# ardumashtun_opl_v1.net
KiCad netlist of a schematic drawn in EAGLE
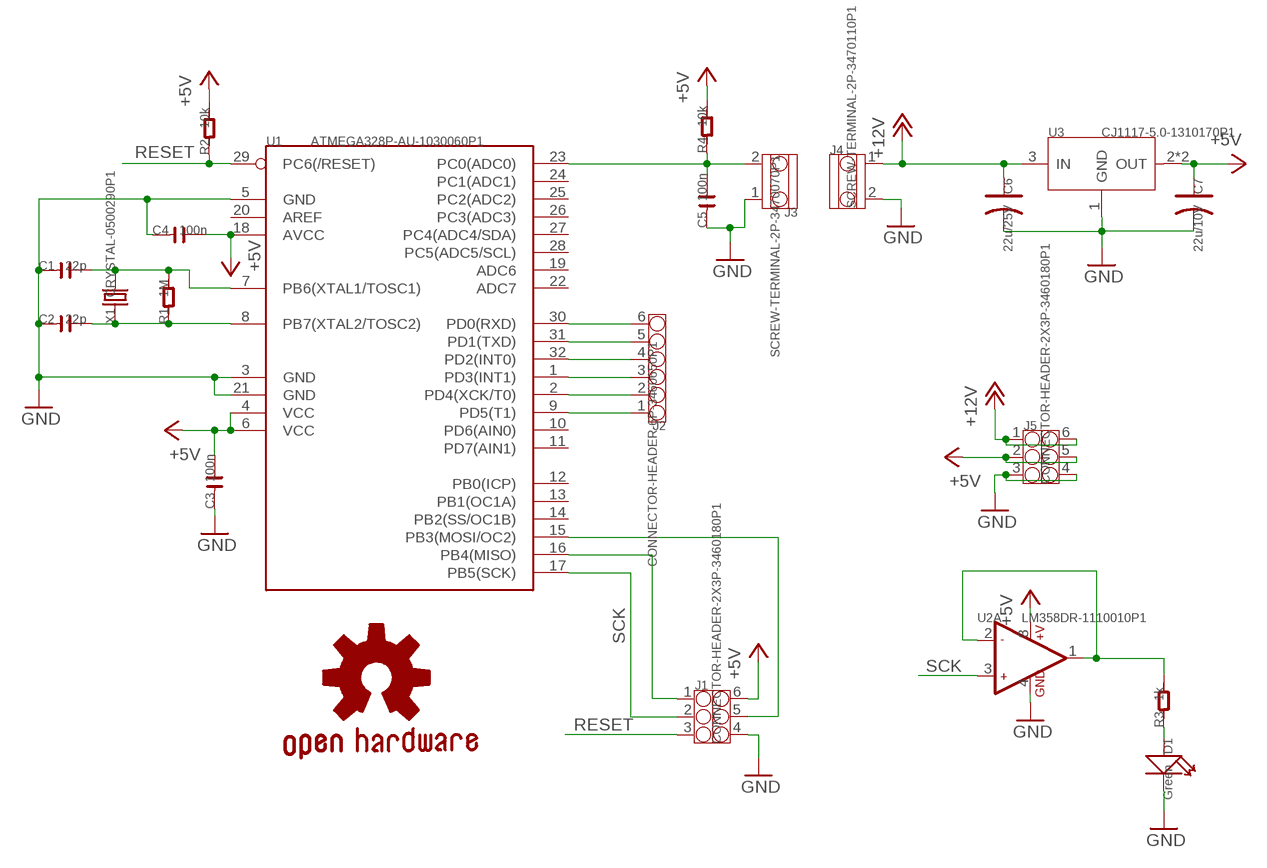
[diagram p0: schematic, sheet 1]

(export (version "E")
  (design (tool "Eeschema 10.0.6"))
  (components
    (comp (ref "C1")
      (value "22p")
      (footprint "eagle-import:C0603")
      (libsource (lib "eagle-import") (part "C-0603"))
    )
    (comp (ref "C2")
      (value "22p")
      (footprint "eagle-import:C0603")
      (libsource (lib "eagle-import") (part "C-0603"))
    )
    (comp (ref "C3")
      (value "100n")
      (footprint "eagle-import:C0603")
      (libsource (lib "eagle-import") (part "C-0603"))
    )
    (comp (ref "C4")
      (value "100n")
      (footprint "eagle-import:C0603")
      (libsource (lib "eagle-import") (part "C-0603"))
    )
    (comp (ref "C5")
      (value "100n")
      (footprint "eagle-import:C0603")
      (libsource (lib "eagle-import") (part "C-0603"))
    )
    (comp (ref "C6")
      (value "22u/25V")
      (footprint "eagle-import:AVX-C")
      (libsource (lib "eagle-import") (part "C-POLAR-C"))
    )
    (comp (ref "C7")
      (value "22u/10V")
      (footprint "eagle-import:AVX-B")
      (libsource (lib "eagle-import") (part "C-POLAR-B"))
    )
    (comp (ref "D1")
      (value "Green")
      (footprint "eagle-import:LED0603")
      (libsource (lib "eagle-import") (part "LED"))
    )
    (comp (ref "GOLD_ORB_SM1")
      (value "OSHWLOGO_GOLD_ORB_SM")
      (footprint "eagle-import:OSHW2")
      (libsource (lib "eagle-import") (part "OSHWLOGO_GOLD_ORB_SM"))
    )
    (comp (ref "J1")
      (value "CONNECTOR-HEADER-2X3P-3460180P1")
      (footprint "eagle-import:2X3P-2.54-2.54-11.6-3.0-BLACK-MALE")
      (libsource (lib "eagle-import") (part "CONNECTOR-HEADER-2X3P-3460180P1"))
    )
    (comp (ref "J2")
      (value "CONNECTOR-HEADER-6P-3460650P1")
      (footprint "eagle-import:1X6P-2.54-2.54-11.6-3.0-BLACK-MALE")
      (libsource (lib "eagle-import") (part "CONNECTOR-HEADER-6P-3460650P1"))
    )
    (comp (ref "J3")
      (value "SCREW-TERMINAL-2P-3470070P1")
      (footprint "eagle-import:2P-3.5")
      (libsource (lib "eagle-import") (part "SCREW-TERMINAL-2P-3470070P1"))
    )
    (comp (ref "J4")
      (value "SCREW-TERMINAL-2P-3470110P1")
      (footprint "eagle-import:2P-5.0")
      (libsource (lib "eagle-import") (part "SCREW-TERMINAL-2P-3470110P1"))
    )
    (comp (ref "J5")
      (value "CONNECTOR-HEADER-2X3P-3460180P1")
      (footprint "eagle-import:2X3P-2.54-2.54-11.6-3.0-BLACK-MALE")
      (libsource (lib "eagle-import") (part "CONNECTOR-HEADER-2X3P-3460180P1"))
    )
    (comp (ref "R1")
      (value "1M")
      (footprint "eagle-import:R0603")
      (libsource (lib "eagle-import") (part "R-0603"))
    )
    (comp (ref "R2")
      (value "10k")
      (footprint "eagle-import:R0603")
      (libsource (lib "eagle-import") (part "R-0603"))
    )
    (comp (ref "R3")
      (value "1k")
      (footprint "eagle-import:R0603")
      (libsource (lib "eagle-import") (part "R-0603"))
    )
    (comp (ref "R4")
      (value "10k")
      (footprint "eagle-import:R0603")
      (libsource (lib "eagle-import") (part "R-0603"))
    )
    (comp (ref "U1")
      (value "ATMEGA328P-AU-1030060P1")
      (footprint "eagle-import:TQFP32")
      (libsource (lib "eagle-import") (part "ATMEGA328P-AU-1030060P1"))
    )
    (comp (ref "U2")
      (value "LM358DR-1110010P1")
      (footprint "eagle-import:SOIC8")
      (libsource (lib "eagle-import") (part "LM358DR-1110010P1"))
    )
    (comp (ref "U3")
      (value "CJ1117-5.0-1310170P1")
      (footprint "eagle-import:SOT223")
      (libsource (lib "eagle-import") (part "CJ1117-5.0-1310170P1"))
    )
    (comp (ref "X1")
      (value "CRYSTAL-0500290P1")
      (footprint "eagle-import:2P-SMD-5.0X3.2")
      (libsource (lib "eagle-import") (part "CRYSTAL-0500290P1"))
    )
  )
  (nets
    (net (code "1") (name "+5V") (class "Default")
      (node (ref "C3") (pin "2") (pinfunction "2_2") (pintype "bidirectional"))
      (node (ref "C4") (pin "2") (pinfunction "2_2") (pintype "bidirectional"))
      (node (ref "C7") (pin "+") (pinfunction "1_+") (pintype "bidirectional"))
      (node (ref "J1") (pin "6") (pinfunction "6_6") (pintype "bidirectional"))
      (node (ref "J5") (pin "2") (pinfunction "2_2") (pintype "bidirectional"))
      (node (ref "J5") (pin "5") (pinfunction "5_5") (pintype "bidirectional"))
      (node (ref "R2") (pin "2") (pinfunction "2_2") (pintype "bidirectional"))
      (node (ref "R4") (pin "2") (pinfunction "2_2") (pintype "bidirectional"))
      (node (ref "U1") (pin "18") (pinfunction "AVCC_18") (pintype "bidirectional"))
      (node (ref "U1") (pin "4") (pinfunction "VCC_4") (pintype "bidirectional"))
      (node (ref "U1") (pin "6") (pinfunction "VCC_6") (pintype "bidirectional"))
      (node (ref "U2") (pin "8") (pinfunction "+V_8") (pintype "power_in"))
      (node (ref "U3") (pin "2") (pinfunction "OUT_2") (pintype "bidirectional"))
      (node (ref "U3") (pin "TER") (pinfunction "OUT_TER") (pintype "bidirectional"))
    )
    (net (code "2") (name "+12V") (class "Default")
      (node (ref "C6") (pin "+") (pinfunction "1_+") (pintype "bidirectional"))
      (node (ref "J4") (pin "1") (pinfunction "1_1") (pintype "bidirectional"))
      (node (ref "J5") (pin "1") (pinfunction "1_1") (pintype "bidirectional"))
      (node (ref "J5") (pin "6") (pinfunction "6_6") (pintype "bidirectional"))
      (node (ref "U3") (pin "3") (pinfunction "IN_3") (pintype "bidirectional"))
    )
    (net (code "3") (name "/RESET") (class "Default")
      (node (ref "J1") (pin "3") (pinfunction "3_3") (pintype "bidirectional"))
      (node (ref "R2") (pin "1") (pinfunction "1_1") (pintype "bidirectional"))
      (node (ref "U1") (pin "29") (pinfunction "PC6(/RESET)_29") (pintype "bidirectional"))
    )
    (net (code "4") (name "/SCK") (class "Default")
      (node (ref "J1") (pin "2") (pinfunction "2_2") (pintype "bidirectional"))
      (node (ref "U1") (pin "17") (pinfunction "PB5(SCK)_17") (pintype "bidirectional"))
      (node (ref "U2") (pin "3") (pinfunction "+IN1_3") (pintype "input"))
    )
    (net (code "5") (name "GND") (class "Default")
      (node (ref "C1") (pin "1") (pinfunction "1_1") (pintype "bidirectional"))
      (node (ref "C2") (pin "1") (pinfunction "1_1") (pintype "bidirectional"))
      (node (ref "C3") (pin "1") (pinfunction "1_1") (pintype "bidirectional"))
      (node (ref "C4") (pin "1") (pinfunction "1_1") (pintype "bidirectional"))
      (node (ref "C5") (pin "1") (pinfunction "1_1") (pintype "bidirectional"))
      (node (ref "C6") (pin "-") (pinfunction "2_-") (pintype "bidirectional"))
      (node (ref "C7") (pin "-") (pinfunction "2_-") (pintype "bidirectional"))
      (node (ref "D1") (pin "-") (pinfunction "-_-") (pintype "passive"))
      (node (ref "J1") (pin "4") (pinfunction "4_4") (pintype "bidirectional"))
      (node (ref "J3") (pin "1") (pinfunction "1_1") (pintype "bidirectional"))
      (node (ref "J4") (pin "2") (pinfunction "2_2") (pintype "bidirectional"))
      (node (ref "J5") (pin "3") (pinfunction "3_3") (pintype "bidirectional"))
      (node (ref "J5") (pin "4") (pinfunction "4_4") (pintype "bidirectional"))
      (node (ref "U1") (pin "21") (pinfunction "GND_21") (pintype "bidirectional"))
      (node (ref "U1") (pin "3") (pinfunction "GND_3") (pintype "bidirectional"))
      (node (ref "U1") (pin "5") (pinfunction "GND_5") (pintype "bidirectional"))
      (node (ref "U2") (pin "4") (pinfunction "GND_4") (pintype "power_in"))
      (node (ref "U3") (pin "1") (pinfunction "GND_1") (pintype "bidirectional"))
    )
    (net (code "6") (name "Net-(D1-Pad+)") (class "Default")
      (node (ref "D1") (pin "+") (pinfunction "+_+") (pintype "passive"))
      (node (ref "R3") (pin "1") (pinfunction "1_1") (pintype "bidirectional"))
    )
    (net (code "7") (name "Net-(U1-PB3(MOSI{slash}OC2))") (class "Default")
      (node (ref "J1") (pin "5") (pinfunction "5_5") (pintype "bidirectional"))
      (node (ref "U1") (pin "15") (pinfunction "PB3(MOSI/OC2)_15") (pintype "bidirectional"))
    )
    (net (code "8") (name "Net-(U1-PB4(MISO))") (class "Default")
      (node (ref "J1") (pin "1") (pinfunction "1_1") (pintype "bidirectional"))
      (node (ref "U1") (pin "16") (pinfunction "PB4(MISO)_16") (pintype "bidirectional"))
    )
    (net (code "9") (name "Net-(U1-PB6(XTAL1{slash}TOSC1))") (class "Default")
      (node (ref "C1") (pin "2") (pinfunction "2_2") (pintype "bidirectional"))
      (node (ref "R1") (pin "2") (pinfunction "2_2") (pintype "bidirectional"))
      (node (ref "U1") (pin "7") (pinfunction "PB6(XTAL1/TOSC1)_7") (pintype "bidirectional"))
      (node (ref "X1") (pin "2") (pinfunction "2_2") (pintype "passive"))
    )
    (net (code "10") (name "Net-(U1-PB7(XTAL2{slash}TOSC2))") (class "Default")
      (node (ref "C2") (pin "2") (pinfunction "2_2") (pintype "bidirectional"))
      (node (ref "R1") (pin "1") (pinfunction "1_1") (pintype "bidirectional"))
      (node (ref "U1") (pin "8") (pinfunction "PB7(XTAL2/TOSC2)_8") (pintype "bidirectional"))
      (node (ref "X1") (pin "1") (pinfunction "1_1") (pintype "passive"))
    )
    (net (code "11") (name "Net-(U1-PC0(ADC0))") (class "Default")
      (node (ref "C5") (pin "2") (pinfunction "2_2") (pintype "bidirectional"))
      (node (ref "J3") (pin "2") (pinfunction "2_2") (pintype "bidirectional"))
      (node (ref "R4") (pin "1") (pinfunction "1_1") (pintype "bidirectional"))
      (node (ref "U1") (pin "23") (pinfunction "PC0(ADC0)_23") (pintype "bidirectional"))
    )
    (net (code "12") (name "Net-(U1-PD0(RXD))") (class "Default")
      (node (ref "J2") (pin "6") (pinfunction "6_6") (pintype "bidirectional"))
      (node (ref "U1") (pin "30") (pinfunction "PD0(RXD)_30") (pintype "bidirectional"))
    )
    (net (code "13") (name "Net-(U1-PD1(TXD))") (class "Default")
      (node (ref "J2") (pin "5") (pinfunction "5_5") (pintype "bidirectional"))
      (node (ref "U1") (pin "31") (pinfunction "PD1(TXD)_31") (pintype "bidirectional"))
    )
    (net (code "14") (name "Net-(U1-PD2(INT0))") (class "Default")
      (node (ref "J2") (pin "4") (pinfunction "4_4") (pintype "bidirectional"))
      (node (ref "U1") (pin "32") (pinfunction "PD2(INT0)_32") (pintype "bidirectional"))
    )
    (net (code "15") (name "Net-(U1-PD3(INT1))") (class "Default")
      (node (ref "J2") (pin "3") (pinfunction "3_3") (pintype "bidirectional"))
      (node (ref "U1") (pin "1") (pinfunction "PD3(INT1)_1") (pintype "bidirectional"))
    )
    (net (code "16") (name "Net-(U1-PD4(XCK{slash}T0))") (class "Default")
      (node (ref "J2") (pin "2") (pinfunction "2_2") (pintype "bidirectional"))
      (node (ref "U1") (pin "2") (pinfunction "PD4(XCK/T0)_2") (pintype "bidirectional"))
    )
    (net (code "17") (name "Net-(U1-PD5(T1))") (class "Default")
      (node (ref "J2") (pin "1") (pinfunction "1_1") (pintype "bidirectional"))
      (node (ref "U1") (pin "9") (pinfunction "PD5(T1)_9") (pintype "bidirectional"))
    )
    (net (code "18") (name "Net-(U2A--IN1)") (class "Default")
      (node (ref "R3") (pin "2") (pinfunction "2_2") (pintype "bidirectional"))
      (node (ref "U2") (pin "1") (pinfunction "OUT1_1") (pintype "output"))
      (node (ref "U2") (pin "2") (pinfunction "-IN1_2") (pintype "input"))
    )
    (net (code "19") (name "unconnected-(U1-ADC6-Pad19)") (class "Default")
      (node (ref "U1") (pin "19") (pinfunction "ADC6_19") (pintype "bidirectional"))
    )
    (net (code "20") (name "unconnected-(U1-ADC7-Pad22)") (class "Default")
      (node (ref "U1") (pin "22") (pinfunction "ADC7_22") (pintype "bidirectional"))
    )
    (net (code "21") (name "unconnected-(U1-AREF-Pad20)") (class "Default")
      (node (ref "U1") (pin "20") (pinfunction "AREF_20") (pintype "bidirectional"))
    )
    (net (code "22") (name "unconnected-(U1-PB0(ICP)-Pad12)") (class "Default")
      (node (ref "U1") (pin "12") (pinfunction "PB0(ICP)_12") (pintype "bidirectional"))
    )
    (net (code "23") (name "unconnected-(U1-PB1(OC1A)-Pad13)") (class "Default")
      (node (ref "U1") (pin "13") (pinfunction "PB1(OC1A)_13") (pintype "bidirectional"))
    )
    (net (code "24") (name "unconnected-(U1-PB2(SS{slash}OC1B)-Pad14)") (class "Default")
      (node (ref "U1") (pin "14") (pinfunction "PB2(SS/OC1B)_14") (pintype "bidirectional"))
    )
    (net (code "25") (name "unconnected-(U1-PC1(ADC1)-Pad24)") (class "Default")
      (node (ref "U1") (pin "24") (pinfunction "PC1(ADC1)_24") (pintype "bidirectional"))
    )
    (net (code "26") (name "unconnected-(U1-PC2(ADC2)-Pad25)") (class "Default")
      (node (ref "U1") (pin "25") (pinfunction "PC2(ADC2)_25") (pintype "bidirectional"))
    )
    (net (code "27") (name "unconnected-(U1-PC3(ADC3)-Pad26)") (class "Default")
      (node (ref "U1") (pin "26") (pinfunction "PC3(ADC3)_26") (pintype "bidirectional"))
    )
    (net (code "28") (name "unconnected-(U1-PC4(ADC4{slash}SDA)-Pad27)") (class "Default")
      (node (ref "U1") (pin "27") (pinfunction "PC4(ADC4/SDA)_27") (pintype "bidirectional"))
    )
    (net (code "29") (name "unconnected-(U1-PC5(ADC5{slash}SCL)-Pad28)") (class "Default")
      (node (ref "U1") (pin "28") (pinfunction "PC5(ADC5/SCL)_28") (pintype "bidirectional"))
    )
    (net (code "30") (name "unconnected-(U1-PD6(AIN0)-Pad10)") (class "Default")
      (node (ref "U1") (pin "10") (pinfunction "PD6(AIN0)_10") (pintype "bidirectional"))
    )
    (net (code "31") (name "unconnected-(U1-PD7(AIN1)-Pad11)") (class "Default")
      (node (ref "U1") (pin "11") (pinfunction "PD7(AIN1)_11") (pintype "bidirectional"))
    )
  )
)
